# moonlamp.net
KiCad netlist of a schematic drawn in EAGLE
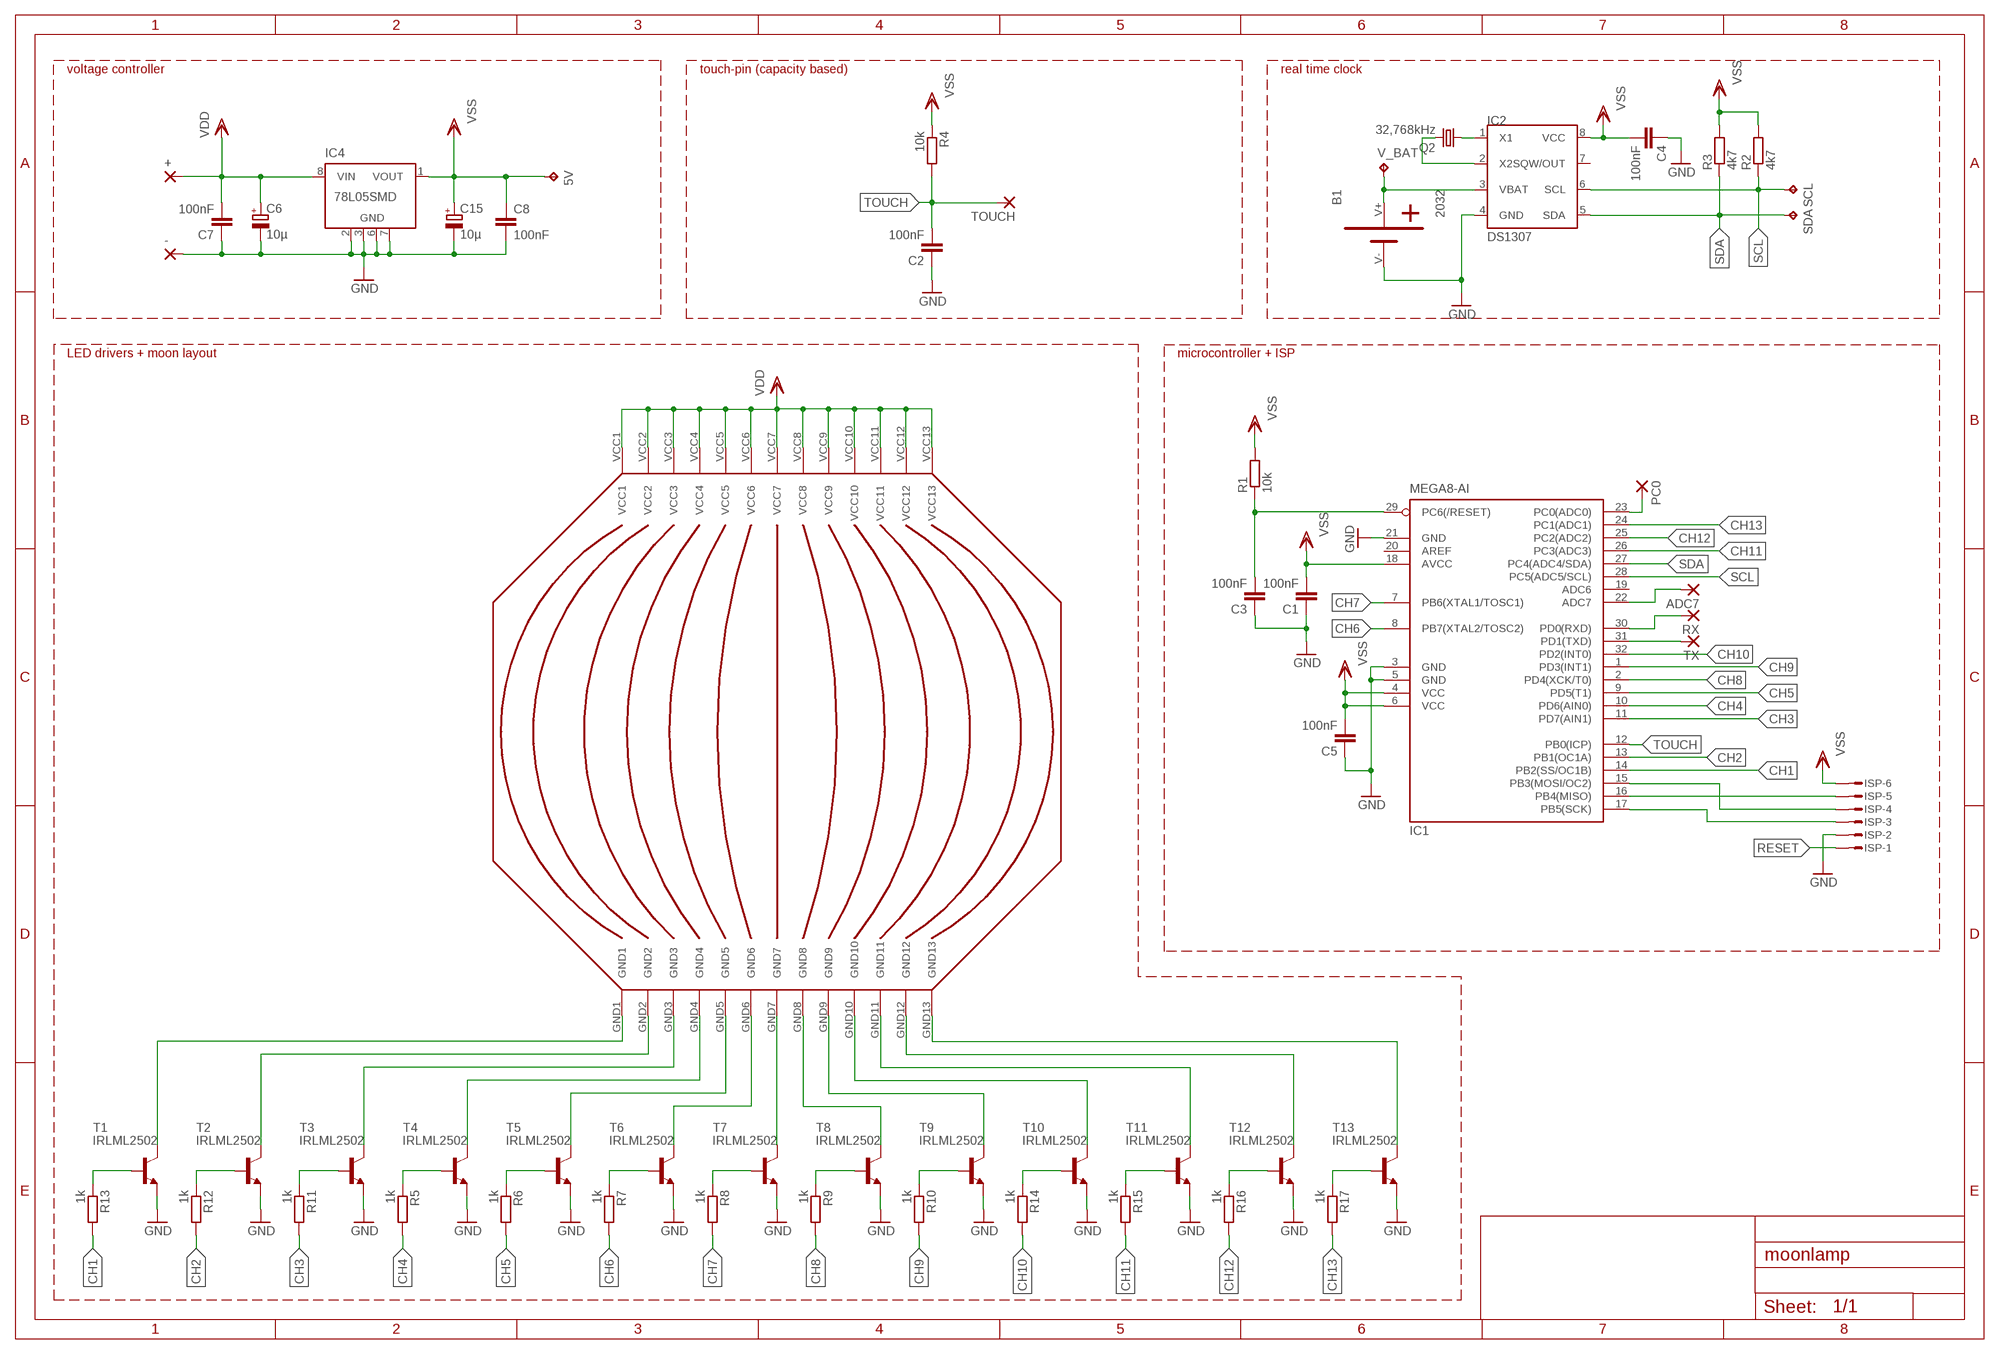
[diagram p0: schematic, sheet 1]

(export (version "E")
  (design (tool "Eeschema 10.0.6"))
  (components
    (comp (ref "+")
      (value "SMD5")
      (footprint "eagle-import:SMD2,54-5,08")
      (libsource (lib "eagle-import") (part "SMD5"))
    )
    (comp (ref "-")
      (value "SMD5")
      (footprint "eagle-import:SMD2,54-5,08")
      (libsource (lib "eagle-import") (part "SMD5"))
    )
    (comp (ref "5V")
      (value "TPB1,27")
      (footprint "eagle-import:B1,27")
      (libsource (lib "eagle-import") (part "TPB1,27"))
    )
    (comp (ref "ADC7")
      (value "SMD2")
      (footprint "eagle-import:SMD1,27-2,54")
      (libsource (lib "eagle-import") (part "SMD2"))
    )
    (comp (ref "B1")
      (value "2032")
      (footprint "eagle-import:2032")
      (libsource (lib "eagle-import") (part "2032"))
    )
    (comp (ref "C1")
      (value "100nF")
      (footprint "eagle-import:C0603")
      (libsource (lib "eagle-import") (part "C-EUC0603"))
    )
    (comp (ref "C2")
      (value "100nF")
      (footprint "eagle-import:C0603")
      (libsource (lib "eagle-import") (part "C-EUC0603"))
    )
    (comp (ref "C3")
      (value "100nF")
      (footprint "eagle-import:C0603K")
      (libsource (lib "eagle-import") (part "C-EUC0603K"))
    )
    (comp (ref "C4")
      (value "100nF")
      (footprint "eagle-import:C0603")
      (libsource (lib "eagle-import") (part "C-EUC0603"))
    )
    (comp (ref "C5")
      (value "100nF")
      (footprint "eagle-import:C0603")
      (libsource (lib "eagle-import") (part "C-EUC0603"))
    )
    (comp (ref "C6")
      (value "10µ")
      (footprint "eagle-import:SMC_A")
      (libsource (lib "eagle-import") (part "CPOL-EUSMCA"))
    )
    (comp (ref "C7")
      (value "100nF")
      (footprint "eagle-import:C0603K")
      (libsource (lib "eagle-import") (part "C-EUC0603K"))
    )
    (comp (ref "C8")
      (value "100nF")
      (footprint "eagle-import:C0603K")
      (libsource (lib "eagle-import") (part "C-EUC0603K"))
    )
    (comp (ref "C15")
      (value "10µ")
      (footprint "eagle-import:SMC_A")
      (libsource (lib "eagle-import") (part "CPOL-EUSMCA"))
    )
    (comp (ref "IC1")
      (value "MEGA8-AI")
      (footprint "eagle-import:TQFP32-08")
      (libsource (lib "eagle-import") (part "MEGA8-AI"))
    )
    (comp (ref "IC2")
      (value "DS1307")
      (footprint "eagle-import:SOIC-8")
      (libsource (lib "eagle-import") (part "DS1307"))
    )
    (comp (ref "IC4")
      (value "78L05SMD")
      (footprint "eagle-import:SO08")
      (libsource (lib "eagle-import") (part "78LSMD05"))
    )
    (comp (ref "ISP")
      (value "MICROMATCH-6SMF")
      (footprint "eagle-import:MMT-F-SMD-6")
      (libsource (lib "eagle-import") (part "MICROMATCH-6SMF"))
    )
    (comp (ref "PC0")
      (value "SMD2")
      (footprint "eagle-import:SMD1,27-2,54")
      (libsource (lib "eagle-import") (part "SMD2"))
    )
    (comp (ref "Q2")
      (value "32,768kHz")
      (footprint "eagle-import:MM20SS")
      (libsource (lib "eagle-import") (part "CRYSTALMM20SS"))
    )
    (comp (ref "R1")
      (value "10k")
      (footprint "eagle-import:R0603")
      (libsource (lib "eagle-import") (part "R-EU_R0603"))
    )
    (comp (ref "R2")
      (value "4k7")
      (footprint "eagle-import:R0603")
      (libsource (lib "eagle-import") (part "R-EU_R0603"))
    )
    (comp (ref "R3")
      (value "4k7")
      (footprint "eagle-import:R0603")
      (libsource (lib "eagle-import") (part "R-EU_R0603"))
    )
    (comp (ref "R4")
      (value "10k")
      (footprint "eagle-import:R0603")
      (libsource (lib "eagle-import") (part "R-EU_R0603"))
    )
    (comp (ref "R5")
      (value "1k")
      (footprint "eagle-import:R1206")
      (libsource (lib "eagle-import") (part "R-EU_R1206"))
    )
    (comp (ref "R6")
      (value "1k")
      (footprint "eagle-import:R1206")
      (libsource (lib "eagle-import") (part "R-EU_R1206"))
    )
    (comp (ref "R7")
      (value "1k")
      (footprint "eagle-import:R1206")
      (libsource (lib "eagle-import") (part "R-EU_R1206"))
    )
    (comp (ref "R8")
      (value "1k")
      (footprint "eagle-import:R1206")
      (libsource (lib "eagle-import") (part "R-EU_R1206"))
    )
    (comp (ref "R9")
      (value "1k")
      (footprint "eagle-import:R1206")
      (libsource (lib "eagle-import") (part "R-EU_R1206"))
    )
    (comp (ref "R10")
      (value "1k")
      (footprint "eagle-import:R1206")
      (libsource (lib "eagle-import") (part "R-EU_R1206"))
    )
    (comp (ref "R11")
      (value "1k")
      (footprint "eagle-import:R1206")
      (libsource (lib "eagle-import") (part "R-EU_R1206"))
    )
    (comp (ref "R12")
      (value "1k")
      (footprint "eagle-import:R1206")
      (libsource (lib "eagle-import") (part "R-EU_R1206"))
    )
    (comp (ref "R13")
      (value "1k")
      (footprint "eagle-import:R1206")
      (libsource (lib "eagle-import") (part "R-EU_R1206"))
    )
    (comp (ref "R14")
      (value "1k")
      (footprint "eagle-import:R1206")
      (libsource (lib "eagle-import") (part "R-EU_R1206"))
    )
    (comp (ref "R15")
      (value "1k")
      (footprint "eagle-import:R1206")
      (libsource (lib "eagle-import") (part "R-EU_R1206"))
    )
    (comp (ref "R16")
      (value "1k")
      (footprint "eagle-import:R1206")
      (libsource (lib "eagle-import") (part "R-EU_R1206"))
    )
    (comp (ref "R17")
      (value "1k")
      (footprint "eagle-import:R1206")
      (libsource (lib "eagle-import") (part "R-EU_R1206"))
    )
    (comp (ref "RX")
      (value "SMD2")
      (footprint "eagle-import:SMD1,27-2,54")
      (libsource (lib "eagle-import") (part "SMD2"))
    )
    (comp (ref "SCL")
      (value "TPB1,27")
      (footprint "eagle-import:B1,27")
      (libsource (lib "eagle-import") (part "TPB1,27"))
    )
    (comp (ref "SDA")
      (value "TPB1,27")
      (footprint "eagle-import:B1,27")
      (libsource (lib "eagle-import") (part "TPB1,27"))
    )
    (comp (ref "T1")
      (value "IRLML2502")
      (footprint "eagle-import:SOT23")
      (libsource (lib "eagle-import") (part "BC847"))
    )
    (comp (ref "T2")
      (value "IRLML2502")
      (footprint "eagle-import:SOT23")
      (libsource (lib "eagle-import") (part "BC847"))
    )
    (comp (ref "T3")
      (value "IRLML2502")
      (footprint "eagle-import:SOT23")
      (libsource (lib "eagle-import") (part "BC847"))
    )
    (comp (ref "T4")
      (value "IRLML2502")
      (footprint "eagle-import:SOT23")
      (libsource (lib "eagle-import") (part "BC847"))
    )
    (comp (ref "T5")
      (value "IRLML2502")
      (footprint "eagle-import:SOT23")
      (libsource (lib "eagle-import") (part "BC847"))
    )
    (comp (ref "T6")
      (value "IRLML2502")
      (footprint "eagle-import:SOT23")
      (libsource (lib "eagle-import") (part "BC847"))
    )
    (comp (ref "T7")
      (value "IRLML2502")
      (footprint "eagle-import:SOT23")
      (libsource (lib "eagle-import") (part "BC847"))
    )
    (comp (ref "T8")
      (value "IRLML2502")
      (footprint "eagle-import:SOT23")
      (libsource (lib "eagle-import") (part "BC847"))
    )
    (comp (ref "T9")
      (value "IRLML2502")
      (footprint "eagle-import:SOT23")
      (libsource (lib "eagle-import") (part "BC847"))
    )
    (comp (ref "T10")
      (value "IRLML2502")
      (footprint "eagle-import:SOT23")
      (libsource (lib "eagle-import") (part "BC847"))
    )
    (comp (ref "T11")
      (value "IRLML2502")
      (footprint "eagle-import:SOT23")
      (libsource (lib "eagle-import") (part "BC847"))
    )
    (comp (ref "T12")
      (value "IRLML2502")
      (footprint "eagle-import:SOT23")
      (libsource (lib "eagle-import") (part "BC847"))
    )
    (comp (ref "T13")
      (value "IRLML2502")
      (footprint "eagle-import:SOT23")
      (libsource (lib "eagle-import") (part "BC847"))
    )
    (comp (ref "TOUCH")
      (value "SMD2")
      (footprint "eagle-import:SMD1,27-2,54")
      (libsource (lib "eagle-import") (part "SMD2"))
    )
    (comp (ref "TX")
      (value "SMD2")
      (footprint "eagle-import:SMD1,27-2,54")
      (libsource (lib "eagle-import") (part "SMD2"))
    )
    (comp (ref "U$1")
      (value "MOON")
      (footprint "eagle-import:MOON")
      (libsource (lib "eagle-import") (part "MOON"))
    )
    (comp (ref "V_BAT")
      (value "TPB1,27")
      (footprint "eagle-import:B1,27")
      (libsource (lib "eagle-import") (part "TPB1,27"))
    )
  )
  (nets
    (net (code "1") (name "CH1") (class "Default")
      (node (ref "IC1") (pin "14") (pinfunction "PB2(SS/OC1B)_14") (pintype "bidirectional"))
      (node (ref "R13") (pin "2") (pinfunction "2_2") (pintype "passive"))
    )
    (net (code "2") (name "CH2") (class "Default")
      (node (ref "IC1") (pin "13") (pinfunction "PB1(OC1A)_13") (pintype "bidirectional"))
      (node (ref "R12") (pin "2") (pinfunction "2_2") (pintype "passive"))
    )
    (net (code "3") (name "CH3") (class "Default")
      (node (ref "IC1") (pin "11") (pinfunction "PD7(AIN1)_11") (pintype "bidirectional"))
      (node (ref "R11") (pin "2") (pinfunction "2_2") (pintype "passive"))
    )
    (net (code "4") (name "CH4") (class "Default")
      (node (ref "IC1") (pin "10") (pinfunction "PD6(AIN0)_10") (pintype "bidirectional"))
      (node (ref "R5") (pin "2") (pinfunction "2_2") (pintype "passive"))
    )
    (net (code "5") (name "CH5") (class "Default")
      (node (ref "IC1") (pin "9") (pinfunction "PD5(T1)_9") (pintype "bidirectional"))
      (node (ref "R6") (pin "2") (pinfunction "2_2") (pintype "passive"))
    )
    (net (code "6") (name "CH6") (class "Default")
      (node (ref "IC1") (pin "8") (pinfunction "PB7(XTAL2/TOSC2)_8") (pintype "bidirectional"))
      (node (ref "R7") (pin "2") (pinfunction "2_2") (pintype "passive"))
    )
    (net (code "7") (name "CH7") (class "Default")
      (node (ref "IC1") (pin "7") (pinfunction "PB6(XTAL1/TOSC1)_7") (pintype "bidirectional"))
      (node (ref "R8") (pin "2") (pinfunction "2_2") (pintype "passive"))
    )
    (net (code "8") (name "CH8") (class "Default")
      (node (ref "IC1") (pin "2") (pinfunction "PD4(XCK/T0)_2") (pintype "bidirectional"))
      (node (ref "R9") (pin "2") (pinfunction "2_2") (pintype "passive"))
    )
    (net (code "9") (name "CH9") (class "Default")
      (node (ref "IC1") (pin "1") (pinfunction "PD3(INT1)_1") (pintype "bidirectional"))
      (node (ref "R10") (pin "2") (pinfunction "2_2") (pintype "passive"))
    )
    (net (code "10") (name "CH10") (class "Default")
      (node (ref "IC1") (pin "32") (pinfunction "PD2(INT0)_32") (pintype "bidirectional"))
      (node (ref "R14") (pin "2") (pinfunction "2_2") (pintype "passive"))
    )
    (net (code "11") (name "CH11") (class "Default")
      (node (ref "IC1") (pin "26") (pinfunction "PC3(ADC3)_26") (pintype "bidirectional"))
      (node (ref "R15") (pin "2") (pinfunction "2_2") (pintype "passive"))
    )
    (net (code "12") (name "CH12") (class "Default")
      (node (ref "IC1") (pin "25") (pinfunction "PC2(ADC2)_25") (pintype "bidirectional"))
      (node (ref "R16") (pin "2") (pinfunction "2_2") (pintype "passive"))
    )
    (net (code "13") (name "CH13") (class "Default")
      (node (ref "IC1") (pin "24") (pinfunction "PC1(ADC1)_24") (pintype "bidirectional"))
      (node (ref "R17") (pin "2") (pinfunction "2_2") (pintype "passive"))
    )
    (net (code "14") (name "GND") (class "Default")
      (node (ref "-") (pin "1") (pinfunction "P_1") (pintype "passive"))
      (node (ref "B1") (pin "V-") (pinfunction "V-_V-") (pintype "bidirectional"))
      (node (ref "C1") (pin "1") (pinfunction "1_1") (pintype "passive"))
      (node (ref "C15") (pin "-") (pinfunction "-_-") (pintype "passive"))
      (node (ref "C2") (pin "1") (pinfunction "1_1") (pintype "passive"))
      (node (ref "C3") (pin "1") (pinfunction "1_1") (pintype "passive"))
      (node (ref "C4") (pin "1") (pinfunction "1_1") (pintype "passive"))
      (node (ref "C5") (pin "1") (pinfunction "1_1") (pintype "passive"))
      (node (ref "C6") (pin "-") (pinfunction "-_-") (pintype "passive"))
      (node (ref "C7") (pin "1") (pinfunction "1_1") (pintype "passive"))
      (node (ref "C8") (pin "2") (pinfunction "2_2") (pintype "passive"))
      (node (ref "IC1") (pin "21") (pinfunction "GND_21") (pintype "power_in"))
      (node (ref "IC1") (pin "3") (pinfunction "GND_3") (pintype "power_in"))
      (node (ref "IC1") (pin "5") (pinfunction "GND_5") (pintype "power_in"))
      (node (ref "IC2") (pin "4") (pinfunction "GND_4") (pintype "power_in"))
      (node (ref "IC4") (pin "2") (pinfunction "GND_2") (pintype "power_in"))
      (node (ref "IC4") (pin "3") (pinfunction "GND_3") (pintype "power_in"))
      (node (ref "IC4") (pin "6") (pinfunction "GND_6") (pintype "power_in"))
      (node (ref "IC4") (pin "7") (pinfunction "GND_7") (pintype "power_in"))
      (node (ref "ISP") (pin "2") (pinfunction "S_2") (pintype "passive"))
      (node (ref "T1") (pin "2") (pinfunction "E_2") (pintype "passive"))
      (node (ref "T10") (pin "2") (pinfunction "E_2") (pintype "passive"))
      (node (ref "T11") (pin "2") (pinfunction "E_2") (pintype "passive"))
      (node (ref "T12") (pin "2") (pinfunction "E_2") (pintype "passive"))
      (node (ref "T13") (pin "2") (pinfunction "E_2") (pintype "passive"))
      (node (ref "T2") (pin "2") (pinfunction "E_2") (pintype "passive"))
      (node (ref "T3") (pin "2") (pinfunction "E_2") (pintype "passive"))
      (node (ref "T4") (pin "2") (pinfunction "E_2") (pintype "passive"))
      (node (ref "T5") (pin "2") (pinfunction "E_2") (pintype "passive"))
      (node (ref "T6") (pin "2") (pinfunction "E_2") (pintype "passive"))
      (node (ref "T7") (pin "2") (pinfunction "E_2") (pintype "passive"))
      (node (ref "T8") (pin "2") (pinfunction "E_2") (pintype "passive"))
      (node (ref "T9") (pin "2") (pinfunction "E_2") (pintype "passive"))
    )
    (net (code "15") (name "Net-(ADC7-P)") (class "Default")
      (node (ref "ADC7") (pin "1") (pinfunction "P_1") (pintype "passive"))
      (node (ref "IC1") (pin "22") (pinfunction "ADC7_22") (pintype "bidirectional"))
    )
    (net (code "16") (name "Net-(IC1-PB3(MOSI{slash}OC2))") (class "Default")
      (node (ref "IC1") (pin "15") (pinfunction "PB3(MOSI/OC2)_15") (pintype "bidirectional"))
      (node (ref "ISP") (pin "4") (pinfunction "S_4") (pintype "passive"))
    )
    (net (code "17") (name "Net-(IC1-PB4(MISO))") (class "Default")
      (node (ref "IC1") (pin "16") (pinfunction "PB4(MISO)_16") (pintype "bidirectional"))
      (node (ref "ISP") (pin "5") (pinfunction "S_5") (pintype "passive"))
    )
    (net (code "18") (name "Net-(IC1-PB5(SCK))") (class "Default")
      (node (ref "IC1") (pin "17") (pinfunction "PB5(SCK)_17") (pintype "bidirectional"))
      (node (ref "ISP") (pin "3") (pinfunction "S_3") (pintype "passive"))
    )
    (net (code "19") (name "Net-(IC1-PC0(ADC0))") (class "Default")
      (node (ref "IC1") (pin "23") (pinfunction "PC0(ADC0)_23") (pintype "bidirectional"))
      (node (ref "PC0") (pin "1") (pinfunction "P_1") (pintype "passive"))
    )
    (net (code "20") (name "Net-(IC1-PD0(RXD))") (class "Default")
      (node (ref "IC1") (pin "30") (pinfunction "PD0(RXD)_30") (pintype "bidirectional"))
      (node (ref "RX") (pin "1") (pinfunction "P_1") (pintype "passive"))
    )
    (net (code "21") (name "Net-(IC1-PD1(TXD))") (class "Default")
      (node (ref "IC1") (pin "31") (pinfunction "PD1(TXD)_31") (pintype "bidirectional"))
      (node (ref "TX") (pin "1") (pinfunction "P_1") (pintype "passive"))
    )
    (net (code "22") (name "Net-(IC2-VBAT)") (class "Default")
      (node (ref "B1") (pin "V+") (pinfunction "V+_V+") (pintype "bidirectional"))
      (node (ref "IC2") (pin "3") (pinfunction "VBAT_3") (pintype "power_in"))
      (node (ref "V_BAT") (pin "TP") (pinfunction "TP_TP") (pintype "input"))
    )
    (net (code "23") (name "Net-(IC2-X1)") (class "Default")
      (node (ref "IC2") (pin "1") (pinfunction "X1_1") (pintype "input"))
      (node (ref "Q2") (pin "1") (pinfunction "1_1") (pintype "passive"))
    )
    (net (code "24") (name "Net-(IC2-X2)") (class "Default")
      (node (ref "IC2") (pin "2") (pinfunction "X2_2") (pintype "output"))
      (node (ref "Q2") (pin "4") (pinfunction "2_4") (pintype "passive"))
    )
    (net (code "25") (name "Net-(T1-B)") (class "Default")
      (node (ref "R13") (pin "1") (pinfunction "1_1") (pintype "passive"))
      (node (ref "T1") (pin "1") (pinfunction "B_1") (pintype "passive"))
    )
    (net (code "26") (name "Net-(T1-C)") (class "Default")
      (node (ref "T1") (pin "3") (pinfunction "C_3") (pintype "passive"))
      (node (ref "U$1") (pin "GND1") (pinfunction "GND1_GND1") (pintype "bidirectional"))
    )
    (net (code "27") (name "Net-(T2-B)") (class "Default")
      (node (ref "R12") (pin "1") (pinfunction "1_1") (pintype "passive"))
      (node (ref "T2") (pin "1") (pinfunction "B_1") (pintype "passive"))
    )
    (net (code "28") (name "Net-(T2-C)") (class "Default")
      (node (ref "T2") (pin "3") (pinfunction "C_3") (pintype "passive"))
      (node (ref "U$1") (pin "GND2") (pinfunction "GND2_GND2") (pintype "bidirectional"))
    )
    (net (code "29") (name "Net-(T3-B)") (class "Default")
      (node (ref "R11") (pin "1") (pinfunction "1_1") (pintype "passive"))
      (node (ref "T3") (pin "1") (pinfunction "B_1") (pintype "passive"))
    )
    (net (code "30") (name "Net-(T3-C)") (class "Default")
      (node (ref "T3") (pin "3") (pinfunction "C_3") (pintype "passive"))
      (node (ref "U$1") (pin "GND3") (pinfunction "GND3_GND3") (pintype "bidirectional"))
    )
    (net (code "31") (name "Net-(T4-B)") (class "Default")
      (node (ref "R5") (pin "1") (pinfunction "1_1") (pintype "passive"))
      (node (ref "T4") (pin "1") (pinfunction "B_1") (pintype "passive"))
    )
    (net (code "32") (name "Net-(T4-C)") (class "Default")
      (node (ref "T4") (pin "3") (pinfunction "C_3") (pintype "passive"))
      (node (ref "U$1") (pin "GND4") (pinfunction "GND4_GND4") (pintype "bidirectional"))
    )
    (net (code "33") (name "Net-(T5-B)") (class "Default")
      (node (ref "R6") (pin "1") (pinfunction "1_1") (pintype "passive"))
      (node (ref "T5") (pin "1") (pinfunction "B_1") (pintype "passive"))
    )
    (net (code "34") (name "Net-(T5-C)") (class "Default")
      (node (ref "T5") (pin "3") (pinfunction "C_3") (pintype "passive"))
      (node (ref "U$1") (pin "GND5") (pinfunction "GND5_GND5") (pintype "bidirectional"))
    )
    (net (code "35") (name "Net-(T6-B)") (class "Default")
      (node (ref "R7") (pin "1") (pinfunction "1_1") (pintype "passive"))
      (node (ref "T6") (pin "1") (pinfunction "B_1") (pintype "passive"))
    )
    (net (code "36") (name "Net-(T6-C)") (class "Default")
      (node (ref "T6") (pin "3") (pinfunction "C_3") (pintype "passive"))
      (node (ref "U$1") (pin "GND6") (pinfunction "GND6_GND6") (pintype "bidirectional"))
    )
    (net (code "37") (name "Net-(T7-B)") (class "Default")
      (node (ref "R8") (pin "1") (pinfunction "1_1") (pintype "passive"))
      (node (ref "T7") (pin "1") (pinfunction "B_1") (pintype "passive"))
    )
    (net (code "38") (name "Net-(T7-C)") (class "Default")
      (node (ref "T7") (pin "3") (pinfunction "C_3") (pintype "passive"))
      (node (ref "U$1") (pin "GND7") (pinfunction "GND7_GND7") (pintype "bidirectional"))
    )
    (net (code "39") (name "Net-(T8-B)") (class "Default")
      (node (ref "R9") (pin "1") (pinfunction "1_1") (pintype "passive"))
      (node (ref "T8") (pin "1") (pinfunction "B_1") (pintype "passive"))
    )
    (net (code "40") (name "Net-(T8-C)") (class "Default")
      (node (ref "T8") (pin "3") (pinfunction "C_3") (pintype "passive"))
      (node (ref "U$1") (pin "GND8") (pinfunction "GND8_GND8") (pintype "bidirectional"))
    )
    (net (code "41") (name "Net-(T9-B)") (class "Default")
      (node (ref "R10") (pin "1") (pinfunction "1_1") (pintype "passive"))
      (node (ref "T9") (pin "1") (pinfunction "B_1") (pintype "passive"))
    )
    (net (code "42") (name "Net-(T9-C)") (class "Default")
      (node (ref "T9") (pin "3") (pinfunction "C_3") (pintype "passive"))
      (node (ref "U$1") (pin "GND9") (pinfunction "GND9_GND9") (pintype "bidirectional"))
    )
    (net (code "43") (name "Net-(T10-B)") (class "Default")
      (node (ref "R14") (pin "1") (pinfunction "1_1") (pintype "passive"))
      (node (ref "T10") (pin "1") (pinfunction "B_1") (pintype "passive"))
    )
    (net (code "44") (name "Net-(T10-C)") (class "Default")
      (node (ref "T10") (pin "3") (pinfunction "C_3") (pintype "passive"))
      (node (ref "U$1") (pin "GND10") (pinfunction "GND10_GND10") (pintype "bidirectional"))
    )
    (net (code "45") (name "Net-(T11-B)") (class "Default")
      (node (ref "R15") (pin "1") (pinfunction "1_1") (pintype "passive"))
      (node (ref "T11") (pin "1") (pinfunction "B_1") (pintype "passive"))
    )
    (net (code "46") (name "Net-(T11-C)") (class "Default")
      (node (ref "T11") (pin "3") (pinfunction "C_3") (pintype "passive"))
      (node (ref "U$1") (pin "GND11") (pinfunction "GND11_GND11") (pintype "bidirectional"))
    )
    (net (code "47") (name "Net-(T12-B)") (class "Default")
      (node (ref "R16") (pin "1") (pinfunction "1_1") (pintype "passive"))
      (node (ref "T12") (pin "1") (pinfunction "B_1") (pintype "passive"))
    )
    (net (code "48") (name "Net-(T12-C)") (class "Default")
      (node (ref "T12") (pin "3") (pinfunction "C_3") (pintype "passive"))
      (node (ref "U$1") (pin "GND12") (pinfunction "GND12_GND12") (pintype "bidirectional"))
    )
    (net (code "49") (name "Net-(T13-B)") (class "Default")
      (node (ref "R17") (pin "1") (pinfunction "1_1") (pintype "passive"))
      (node (ref "T13") (pin "1") (pinfunction "B_1") (pintype "passive"))
    )
    (net (code "50") (name "Net-(T13-C)") (class "Default")
      (node (ref "T13") (pin "3") (pinfunction "C_3") (pintype "passive"))
      (node (ref "U$1") (pin "GND13") (pinfunction "GND13_GND13") (pintype "bidirectional"))
    )
    (net (code "51") (name "RESET") (class "Default")
      (node (ref "C3") (pin "2") (pinfunction "2_2") (pintype "passive"))
      (node (ref "IC1") (pin "29") (pinfunction "PC6(/RESET)_29") (pintype "bidirectional"))
      (node (ref "ISP") (pin "1") (pinfunction "S_1") (pintype "passive"))
      (node (ref "R1") (pin "1") (pinfunction "1_1") (pintype "passive"))
    )
    (net (code "52") (name "SCL") (class "Default")
      (node (ref "IC1") (pin "28") (pinfunction "PC5(ADC5/SCL)_28") (pintype "bidirectional"))
      (node (ref "IC2") (pin "6") (pinfunction "SCL_6") (pintype "input"))
      (node (ref "R2") (pin "1") (pinfunction "1_1") (pintype "passive"))
      (node (ref "SCL") (pin "TP") (pinfunction "TP_TP") (pintype "input"))
    )
    (net (code "53") (name "SDA") (class "Default")
      (node (ref "IC1") (pin "27") (pinfunction "PC4(ADC4/SDA)_27") (pintype "bidirectional"))
      (node (ref "IC2") (pin "5") (pinfunction "SDA_5") (pintype "bidirectional"))
      (node (ref "R3") (pin "1") (pinfunction "1_1") (pintype "passive"))
      (node (ref "SDA") (pin "TP") (pinfunction "TP_TP") (pintype "input"))
    )
    (net (code "54") (name "TOUCH") (class "Default")
      (node (ref "C2") (pin "2") (pinfunction "2_2") (pintype "passive"))
      (node (ref "IC1") (pin "12") (pinfunction "PB0(ICP)_12") (pintype "bidirectional"))
      (node (ref "R4") (pin "2") (pinfunction "2_2") (pintype "passive"))
      (node (ref "TOUCH") (pin "1") (pinfunction "P_1") (pintype "passive"))
    )
    (net (code "55") (name "VDD") (class "Default")
      (node (ref "+") (pin "1") (pinfunction "P_1") (pintype "passive"))
      (node (ref "C6") (pin "+") (pinfunction "+_+") (pintype "passive"))
      (node (ref "C7") (pin "2") (pinfunction "2_2") (pintype "passive"))
      (node (ref "IC4") (pin "8") (pinfunction "VIN_8") (pintype "passive"))
      (node (ref "U$1") (pin "VCC1") (pinfunction "VCC1_VCC1") (pintype "bidirectional"))
      (node (ref "U$1") (pin "VCC10") (pinfunction "VCC10_VCC10") (pintype "bidirectional"))
      (node (ref "U$1") (pin "VCC11") (pinfunction "VCC11_VCC11") (pintype "bidirectional"))
      (node (ref "U$1") (pin "VCC12") (pinfunction "VCC12_VCC12") (pintype "bidirectional"))
      (node (ref "U$1") (pin "VCC13") (pinfunction "VCC13_VCC13") (pintype "bidirectional"))
      (node (ref "U$1") (pin "VCC2") (pinfunction "VCC2_VCC2") (pintype "bidirectional"))
      (node (ref "U$1") (pin "VCC3") (pinfunction "VCC3_VCC3") (pintype "bidirectional"))
      (node (ref "U$1") (pin "VCC4") (pinfunction "VCC4_VCC4") (pintype "bidirectional"))
      (node (ref "U$1") (pin "VCC5") (pinfunction "VCC5_VCC5") (pintype "bidirectional"))
      (node (ref "U$1") (pin "VCC6") (pinfunction "VCC6_VCC6") (pintype "bidirectional"))
      (node (ref "U$1") (pin "VCC7") (pinfunction "VCC7_VCC7") (pintype "bidirectional"))
      (node (ref "U$1") (pin "VCC8") (pinfunction "VCC8_VCC8") (pintype "bidirectional"))
      (node (ref "U$1") (pin "VCC9") (pinfunction "VCC9_VCC9") (pintype "bidirectional"))
    )
    (net (code "56") (name "VSS") (class "Default")
      (node (ref "5V") (pin "TP") (pinfunction "TP_TP") (pintype "input"))
      (node (ref "C1") (pin "2") (pinfunction "2_2") (pintype "passive"))
      (node (ref "C15") (pin "+") (pinfunction "+_+") (pintype "passive"))
      (node (ref "C4") (pin "2") (pinfunction "2_2") (pintype "passive"))
      (node (ref "C5") (pin "2") (pinfunction "2_2") (pintype "passive"))
      (node (ref "C8") (pin "1") (pinfunction "1_1") (pintype "passive"))
      (node (ref "IC1") (pin "18") (pinfunction "AVCC_18") (pintype "power_in"))
      (node (ref "IC1") (pin "4") (pinfunction "VCC_4") (pintype "power_in"))
      (node (ref "IC1") (pin "6") (pinfunction "VCC_6") (pintype "power_in"))
      (node (ref "IC2") (pin "8") (pinfunction "VCC_8") (pintype "power_in"))
      (node (ref "IC4") (pin "1") (pinfunction "VOUT_1") (pintype "output"))
      (node (ref "ISP") (pin "6") (pinfunction "S_6") (pintype "passive"))
      (node (ref "R1") (pin "2") (pinfunction "2_2") (pintype "passive"))
      (node (ref "R2") (pin "2") (pinfunction "2_2") (pintype "passive"))
      (node (ref "R3") (pin "2") (pinfunction "2_2") (pintype "passive"))
      (node (ref "R4") (pin "1") (pinfunction "1_1") (pintype "passive"))
    )
    (net (code "57") (name "unconnected-(IC1-ADC6-Pad19)") (class "Default")
      (node (ref "IC1") (pin "19") (pinfunction "ADC6_19") (pintype "bidirectional"))
    )
    (net (code "58") (name "unconnected-(IC1-AREF-Pad20)") (class "Default")
      (node (ref "IC1") (pin "20") (pinfunction "AREF_20") (pintype "passive"))
    )
    (net (code "59") (name "unconnected-(IC2-SQW{slash}OUT-Pad7)") (class "Default")
      (node (ref "IC2") (pin "7") (pinfunction "SQW/OUT_7") (pintype "output"))
    )
  )
)
